# triboard-tc3x7-extension.net
KiCad netlist of a schematic drawn in Altium Designer
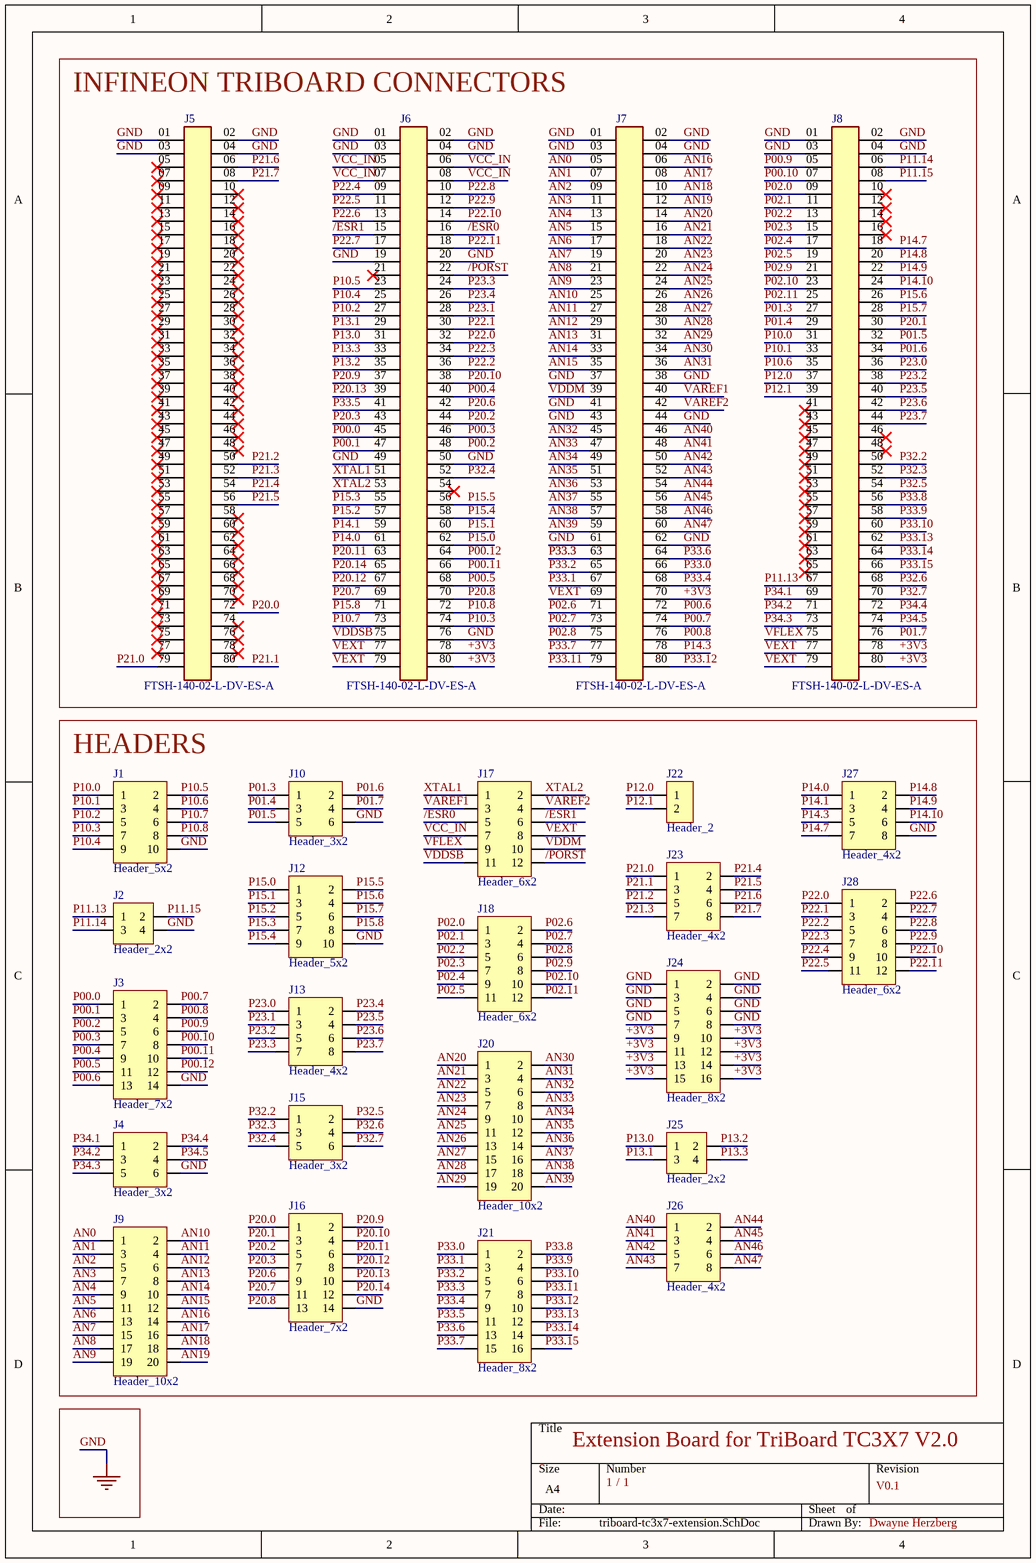
[diagram p0: triboard-tc3x7-extension.SchDoc]

(export (version "E")
  (design (tool "Eeschema 10.0.6"))
  (components
    (comp (ref "J1")
      (value "Header_5x2")
      (footprint "header_5x2")
      (libsource (lib "Shield") (part "Header_5x2"))
    )
    (comp (ref "J2")
      (value "Header_2x2")
      (footprint "Header_2x2")
      (libsource (lib "Shield") (part "Header_2x2"))
    )
    (comp (ref "J3")
      (value "Header_7x2")
      (footprint "header_7x2")
      (libsource (lib "Shield") (part "Header_7x2"))
    )
    (comp (ref "J4")
      (value "Header_3x2")
      (footprint "Header_3x2")
      (libsource (lib "Shield") (part "Header_3x2"))
    )
    (comp (ref "J5")
      (value "FTSH-140-02-L-DV-ES-A")
      (footprint "SAMTEC_FTSH-140-XX-XXX-DV-ES-A")
      (description "Board Connector")
      (fields (field (name "MANUFACTURER") "Samtec"))
      (libsource (lib "Shield") (part "FTSH-140-02-L-DV-ES-A"))
    )
    (comp (ref "J6")
      (value "FTSH-140-02-L-DV-ES-A")
      (footprint "SAMTEC_FTSH-140-XX-XXX-DV-ES-A")
      (description "Board Connector")
      (fields (field (name "MANUFACTURER") "Samtec"))
      (libsource (lib "Shield") (part "FTSH-140-02-L-DV-ES-A"))
    )
    (comp (ref "J7")
      (value "FTSH-140-02-L-DV-ES-A")
      (footprint "SAMTEC_FTSH-140-XX-XXX-DV-ES-A")
      (description "Board Connector")
      (fields (field (name "MANUFACTURER") "Samtec"))
      (libsource (lib "Shield") (part "FTSH-140-02-L-DV-ES-A"))
    )
    (comp (ref "J8")
      (value "FTSH-140-02-L-DV-ES-A")
      (footprint "SAMTEC_FTSH-140-XX-XXX-DV-ES-A")
      (description "Board Connector")
      (fields (field (name "MANUFACTURER") "Samtec"))
      (libsource (lib "Shield") (part "FTSH-140-02-L-DV-ES-A"))
    )
    (comp (ref "J9")
      (value "Header_10x2")
      (footprint "Header_10x2")
      (libsource (lib "Shield") (part "Header_10x2"))
    )
    (comp (ref "J10")
      (value "Header_3x2")
      (footprint "Header_3x2")
      (libsource (lib "Shield") (part "Header_3x2"))
    )
    (comp (ref "J12")
      (value "Header_5x2")
      (footprint "header_5x2")
      (libsource (lib "Shield") (part "Header_5x2"))
    )
    (comp (ref "J13")
      (value "Header_4x2")
      (footprint "header_4x2")
      (libsource (lib "Shield") (part "Header_4x2"))
    )
    (comp (ref "J15")
      (value "Header_3x2")
      (footprint "Header_3x2")
      (libsource (lib "Shield") (part "Header_3x2"))
    )
    (comp (ref "J16")
      (value "Header_7x2")
      (footprint "header_7x2")
      (libsource (lib "Shield") (part "Header_7x2"))
    )
    (comp (ref "J17")
      (value "Header_6x2")
      (footprint "header_6x2")
      (libsource (lib "Shield") (part "Header_6x2"))
    )
    (comp (ref "J18")
      (value "Header_6x2")
      (footprint "header_6x2")
      (libsource (lib "Shield") (part "Header_6x2"))
    )
    (comp (ref "J20")
      (value "Header_10x2")
      (footprint "Header_10x2")
      (libsource (lib "Shield") (part "Header_10x2"))
    )
    (comp (ref "J21")
      (value "Header_8x2")
      (footprint "header_8x2")
      (libsource (lib "Shield") (part "Header_8x2"))
    )
    (comp (ref "J22") (value "Header_2") (footprint "HEADER_2") (libsource (lib "Shield") (part "Header_2")))
    (comp (ref "J23")
      (value "Header_4x2")
      (footprint "header_4x2")
      (libsource (lib "Shield") (part "Header_4x2"))
    )
    (comp (ref "J24")
      (value "Header_8x2")
      (footprint "header_8x2")
      (libsource (lib "Shield") (part "Header_8x2"))
    )
    (comp (ref "J25")
      (value "Header_2x2")
      (footprint "Header_2x2")
      (libsource (lib "Shield") (part "Header_2x2"))
    )
    (comp (ref "J26")
      (value "Header_4x2")
      (footprint "header_4x2")
      (libsource (lib "Shield") (part "Header_4x2"))
    )
    (comp (ref "J27")
      (value "Header_4x2")
      (footprint "header_4x2")
      (libsource (lib "Shield") (part "Header_4x2"))
    )
    (comp (ref "J28")
      (value "Header_6x2")
      (footprint "header_6x2")
      (libsource (lib "Shield") (part "Header_6x2"))
    )
  )
  (nets
    (net (code "1") (name "/+3V3") (class "Default")
      (node (ref "J24") (pin "10") (pinfunction "10_10") (pintype "passive"))
      (node (ref "J24") (pin "11") (pinfunction "11_11") (pintype "passive"))
      (node (ref "J24") (pin "12") (pinfunction "12_12") (pintype "passive"))
      (node (ref "J24") (pin "13") (pinfunction "13_13") (pintype "passive"))
      (node (ref "J24") (pin "14") (pinfunction "14_14") (pintype "passive"))
      (node (ref "J24") (pin "15") (pinfunction "15_15") (pintype "passive"))
      (node (ref "J24") (pin "16") (pinfunction "16_16") (pintype "passive"))
      (node (ref "J24") (pin "9") (pinfunction "9_9") (pintype "passive"))
      (node (ref "J6") (pin "78") (pinfunction "78_78") (pintype "passive"))
      (node (ref "J6") (pin "80") (pinfunction "80_80") (pintype "passive"))
      (node (ref "J7") (pin "70") (pinfunction "70_70") (pintype "passive"))
      (node (ref "J8") (pin "78") (pinfunction "78_78") (pintype "passive"))
      (node (ref "J8") (pin "80") (pinfunction "80_80") (pintype "passive"))
    )
    (net (code "2") (name "/AN0") (class "Default")
      (node (ref "J7") (pin "05") (pinfunction "05_05") (pintype "passive"))
      (node (ref "J9") (pin "1") (pinfunction "1_1") (pintype "passive"))
    )
    (net (code "3") (name "/AN1") (class "Default")
      (node (ref "J7") (pin "07") (pinfunction "07_07") (pintype "passive"))
      (node (ref "J9") (pin "3") (pinfunction "3_3") (pintype "passive"))
    )
    (net (code "4") (name "/AN2") (class "Default")
      (node (ref "J7") (pin "09") (pinfunction "09_09") (pintype "passive"))
      (node (ref "J9") (pin "5") (pinfunction "5_5") (pintype "passive"))
    )
    (net (code "5") (name "/AN3") (class "Default")
      (node (ref "J7") (pin "11") (pinfunction "11_11") (pintype "passive"))
      (node (ref "J9") (pin "7") (pinfunction "7_7") (pintype "passive"))
    )
    (net (code "6") (name "/AN4") (class "Default")
      (node (ref "J7") (pin "13") (pinfunction "13_13") (pintype "passive"))
      (node (ref "J9") (pin "9") (pinfunction "9_9") (pintype "passive"))
    )
    (net (code "7") (name "/AN5") (class "Default")
      (node (ref "J7") (pin "15") (pinfunction "15_15") (pintype "passive"))
      (node (ref "J9") (pin "11") (pinfunction "11_11") (pintype "passive"))
    )
    (net (code "8") (name "/AN6") (class "Default")
      (node (ref "J7") (pin "17") (pinfunction "17_17") (pintype "passive"))
      (node (ref "J9") (pin "13") (pinfunction "13_13") (pintype "passive"))
    )
    (net (code "9") (name "/AN7") (class "Default")
      (node (ref "J7") (pin "19") (pinfunction "19_19") (pintype "passive"))
      (node (ref "J9") (pin "15") (pinfunction "15_15") (pintype "passive"))
    )
    (net (code "10") (name "/AN8") (class "Default")
      (node (ref "J7") (pin "21") (pinfunction "21_21") (pintype "passive"))
      (node (ref "J9") (pin "17") (pinfunction "17_17") (pintype "passive"))
    )
    (net (code "11") (name "/AN9") (class "Default")
      (node (ref "J7") (pin "23") (pinfunction "23_23") (pintype "passive"))
      (node (ref "J9") (pin "19") (pinfunction "19_19") (pintype "passive"))
    )
    (net (code "12") (name "/AN10") (class "Default")
      (node (ref "J7") (pin "25") (pinfunction "25_25") (pintype "passive"))
      (node (ref "J9") (pin "2") (pinfunction "2_2") (pintype "passive"))
    )
    (net (code "13") (name "/AN11") (class "Default")
      (node (ref "J7") (pin "27") (pinfunction "27_27") (pintype "passive"))
      (node (ref "J9") (pin "4") (pinfunction "4_4") (pintype "passive"))
    )
    (net (code "14") (name "/AN12") (class "Default")
      (node (ref "J7") (pin "29") (pinfunction "29_29") (pintype "passive"))
      (node (ref "J9") (pin "6") (pinfunction "6_6") (pintype "passive"))
    )
    (net (code "15") (name "/AN13") (class "Default")
      (node (ref "J7") (pin "31") (pinfunction "31_31") (pintype "passive"))
      (node (ref "J9") (pin "8") (pinfunction "8_8") (pintype "passive"))
    )
    (net (code "16") (name "/AN14") (class "Default")
      (node (ref "J7") (pin "33") (pinfunction "33_33") (pintype "passive"))
      (node (ref "J9") (pin "10") (pinfunction "10_10") (pintype "passive"))
    )
    (net (code "17") (name "/AN15") (class "Default")
      (node (ref "J7") (pin "35") (pinfunction "35_35") (pintype "passive"))
      (node (ref "J9") (pin "12") (pinfunction "12_12") (pintype "passive"))
    )
    (net (code "18") (name "/AN16") (class "Default")
      (node (ref "J7") (pin "06") (pinfunction "06_06") (pintype "passive"))
      (node (ref "J9") (pin "14") (pinfunction "14_14") (pintype "passive"))
    )
    (net (code "19") (name "/AN17") (class "Default")
      (node (ref "J7") (pin "08") (pinfunction "08_08") (pintype "passive"))
      (node (ref "J9") (pin "16") (pinfunction "16_16") (pintype "passive"))
    )
    (net (code "20") (name "/AN18") (class "Default")
      (node (ref "J7") (pin "10") (pinfunction "10_10") (pintype "passive"))
      (node (ref "J9") (pin "18") (pinfunction "18_18") (pintype "passive"))
    )
    (net (code "21") (name "/AN19") (class "Default")
      (node (ref "J7") (pin "12") (pinfunction "12_12") (pintype "passive"))
      (node (ref "J9") (pin "20") (pinfunction "20_20") (pintype "passive"))
    )
    (net (code "22") (name "/AN20") (class "Default")
      (node (ref "J20") (pin "1") (pinfunction "1_1") (pintype "passive"))
      (node (ref "J7") (pin "14") (pinfunction "14_14") (pintype "passive"))
    )
    (net (code "23") (name "/AN21") (class "Default")
      (node (ref "J20") (pin "3") (pinfunction "3_3") (pintype "passive"))
      (node (ref "J7") (pin "16") (pinfunction "16_16") (pintype "passive"))
    )
    (net (code "24") (name "/AN22") (class "Default")
      (node (ref "J20") (pin "5") (pinfunction "5_5") (pintype "passive"))
      (node (ref "J7") (pin "18") (pinfunction "18_18") (pintype "passive"))
    )
    (net (code "25") (name "/AN23") (class "Default")
      (node (ref "J20") (pin "7") (pinfunction "7_7") (pintype "passive"))
      (node (ref "J7") (pin "20") (pinfunction "20_20") (pintype "passive"))
    )
    (net (code "26") (name "/AN24") (class "Default")
      (node (ref "J20") (pin "9") (pinfunction "9_9") (pintype "passive"))
      (node (ref "J7") (pin "22") (pinfunction "22_22") (pintype "passive"))
    )
    (net (code "27") (name "/AN25") (class "Default")
      (node (ref "J20") (pin "11") (pinfunction "11_11") (pintype "passive"))
      (node (ref "J7") (pin "24") (pinfunction "24_24") (pintype "passive"))
    )
    (net (code "28") (name "/AN26") (class "Default")
      (node (ref "J20") (pin "13") (pinfunction "13_13") (pintype "passive"))
      (node (ref "J7") (pin "26") (pinfunction "26_26") (pintype "passive"))
    )
    (net (code "29") (name "/AN27") (class "Default")
      (node (ref "J20") (pin "15") (pinfunction "15_15") (pintype "passive"))
      (node (ref "J7") (pin "28") (pinfunction "28_28") (pintype "passive"))
    )
    (net (code "30") (name "/AN28") (class "Default")
      (node (ref "J20") (pin "17") (pinfunction "17_17") (pintype "passive"))
      (node (ref "J7") (pin "30") (pinfunction "30_30") (pintype "passive"))
    )
    (net (code "31") (name "/AN29") (class "Default")
      (node (ref "J20") (pin "19") (pinfunction "19_19") (pintype "passive"))
      (node (ref "J7") (pin "32") (pinfunction "32_32") (pintype "passive"))
    )
    (net (code "32") (name "/AN30") (class "Default")
      (node (ref "J20") (pin "2") (pinfunction "2_2") (pintype "passive"))
      (node (ref "J7") (pin "34") (pinfunction "34_34") (pintype "passive"))
    )
    (net (code "33") (name "/AN31") (class "Default")
      (node (ref "J20") (pin "4") (pinfunction "4_4") (pintype "passive"))
      (node (ref "J7") (pin "36") (pinfunction "36_36") (pintype "passive"))
    )
    (net (code "34") (name "/AN32") (class "Default")
      (node (ref "J20") (pin "6") (pinfunction "6_6") (pintype "passive"))
      (node (ref "J7") (pin "45") (pinfunction "45_45") (pintype "passive"))
    )
    (net (code "35") (name "/AN33") (class "Default")
      (node (ref "J20") (pin "8") (pinfunction "8_8") (pintype "passive"))
      (node (ref "J7") (pin "47") (pinfunction "47_47") (pintype "passive"))
    )
    (net (code "36") (name "/AN34") (class "Default")
      (node (ref "J20") (pin "10") (pinfunction "10_10") (pintype "passive"))
      (node (ref "J7") (pin "49") (pinfunction "49_49") (pintype "passive"))
    )
    (net (code "37") (name "/AN35") (class "Default")
      (node (ref "J20") (pin "12") (pinfunction "12_12") (pintype "passive"))
      (node (ref "J7") (pin "51") (pinfunction "51_51") (pintype "passive"))
    )
    (net (code "38") (name "/AN36") (class "Default")
      (node (ref "J20") (pin "14") (pinfunction "14_14") (pintype "passive"))
      (node (ref "J7") (pin "53") (pinfunction "53_53") (pintype "passive"))
    )
    (net (code "39") (name "/AN37") (class "Default")
      (node (ref "J20") (pin "16") (pinfunction "16_16") (pintype "passive"))
      (node (ref "J7") (pin "55") (pinfunction "55_55") (pintype "passive"))
    )
    (net (code "40") (name "/AN38") (class "Default")
      (node (ref "J20") (pin "18") (pinfunction "18_18") (pintype "passive"))
      (node (ref "J7") (pin "57") (pinfunction "57_57") (pintype "passive"))
    )
    (net (code "41") (name "/AN39") (class "Default")
      (node (ref "J20") (pin "20") (pinfunction "20_20") (pintype "passive"))
      (node (ref "J7") (pin "59") (pinfunction "59_59") (pintype "passive"))
    )
    (net (code "42") (name "/AN40") (class "Default")
      (node (ref "J26") (pin "1") (pinfunction "1_1") (pintype "passive"))
      (node (ref "J7") (pin "46") (pinfunction "46_46") (pintype "passive"))
    )
    (net (code "43") (name "/AN41") (class "Default")
      (node (ref "J26") (pin "3") (pinfunction "3_3") (pintype "passive"))
      (node (ref "J7") (pin "48") (pinfunction "48_48") (pintype "passive"))
    )
    (net (code "44") (name "/AN42") (class "Default")
      (node (ref "J26") (pin "5") (pinfunction "5_5") (pintype "passive"))
      (node (ref "J7") (pin "50") (pinfunction "50_50") (pintype "passive"))
    )
    (net (code "45") (name "/AN43") (class "Default")
      (node (ref "J26") (pin "7") (pinfunction "7_7") (pintype "passive"))
      (node (ref "J7") (pin "52") (pinfunction "52_52") (pintype "passive"))
    )
    (net (code "46") (name "/AN44") (class "Default")
      (node (ref "J26") (pin "2") (pinfunction "2_2") (pintype "passive"))
      (node (ref "J7") (pin "54") (pinfunction "54_54") (pintype "passive"))
    )
    (net (code "47") (name "/AN45") (class "Default")
      (node (ref "J26") (pin "4") (pinfunction "4_4") (pintype "passive"))
      (node (ref "J7") (pin "56") (pinfunction "56_56") (pintype "passive"))
    )
    (net (code "48") (name "/AN46") (class "Default")
      (node (ref "J26") (pin "6") (pinfunction "6_6") (pintype "passive"))
      (node (ref "J7") (pin "58") (pinfunction "58_58") (pintype "passive"))
    )
    (net (code "49") (name "/AN47") (class "Default")
      (node (ref "J26") (pin "8") (pinfunction "8_8") (pintype "passive"))
      (node (ref "J7") (pin "60") (pinfunction "60_60") (pintype "passive"))
    )
    (net (code "50") (name "/P00.0") (class "Default")
      (node (ref "J3") (pin "1") (pinfunction "1_1") (pintype "passive"))
      (node (ref "J6") (pin "45") (pinfunction "45_45") (pintype "passive"))
    )
    (net (code "51") (name "/P00.1") (class "Default")
      (node (ref "J3") (pin "3") (pinfunction "3_3") (pintype "passive"))
      (node (ref "J6") (pin "47") (pinfunction "47_47") (pintype "passive"))
    )
    (net (code "52") (name "/P00.2") (class "Default")
      (node (ref "J3") (pin "5") (pinfunction "5_5") (pintype "passive"))
      (node (ref "J6") (pin "48") (pinfunction "48_48") (pintype "passive"))
    )
    (net (code "53") (name "/P00.3") (class "Default")
      (node (ref "J3") (pin "7") (pinfunction "7_7") (pintype "passive"))
      (node (ref "J6") (pin "46") (pinfunction "46_46") (pintype "passive"))
    )
    (net (code "54") (name "/P00.4") (class "Default")
      (node (ref "J3") (pin "9") (pinfunction "9_9") (pintype "passive"))
      (node (ref "J6") (pin "40") (pinfunction "40_40") (pintype "passive"))
    )
    (net (code "55") (name "/P00.5") (class "Default")
      (node (ref "J3") (pin "11") (pinfunction "11_11") (pintype "passive"))
      (node (ref "J6") (pin "68") (pinfunction "68_68") (pintype "passive"))
    )
    (net (code "56") (name "/P00.6") (class "Default")
      (node (ref "J3") (pin "13") (pinfunction "13_13") (pintype "passive"))
      (node (ref "J7") (pin "72") (pinfunction "72_72") (pintype "passive"))
    )
    (net (code "57") (name "/P00.7") (class "Default")
      (node (ref "J3") (pin "2") (pinfunction "2_2") (pintype "passive"))
      (node (ref "J7") (pin "74") (pinfunction "74_74") (pintype "passive"))
    )
    (net (code "58") (name "/P00.8") (class "Default")
      (node (ref "J3") (pin "4") (pinfunction "4_4") (pintype "passive"))
      (node (ref "J7") (pin "76") (pinfunction "76_76") (pintype "passive"))
    )
    (net (code "59") (name "/P00.9") (class "Default")
      (node (ref "J3") (pin "6") (pinfunction "6_6") (pintype "passive"))
      (node (ref "J8") (pin "05") (pinfunction "05_05") (pintype "passive"))
    )
    (net (code "60") (name "/P00.10") (class "Default")
      (node (ref "J3") (pin "8") (pinfunction "8_8") (pintype "passive"))
      (node (ref "J8") (pin "07") (pinfunction "07_07") (pintype "passive"))
    )
    (net (code "61") (name "/P00.11") (class "Default")
      (node (ref "J3") (pin "10") (pinfunction "10_10") (pintype "passive"))
      (node (ref "J6") (pin "66") (pinfunction "66_66") (pintype "passive"))
    )
    (net (code "62") (name "/P00.12") (class "Default")
      (node (ref "J3") (pin "12") (pinfunction "12_12") (pintype "passive"))
      (node (ref "J6") (pin "64") (pinfunction "64_64") (pintype "passive"))
    )
    (net (code "63") (name "/P01.3") (class "Default")
      (node (ref "J10") (pin "1") (pinfunction "1_1") (pintype "passive"))
      (node (ref "J8") (pin "27") (pinfunction "27_27") (pintype "passive"))
    )
    (net (code "64") (name "/P01.4") (class "Default")
      (node (ref "J10") (pin "3") (pinfunction "3_3") (pintype "passive"))
      (node (ref "J8") (pin "29") (pinfunction "29_29") (pintype "passive"))
    )
    (net (code "65") (name "/P01.5") (class "Default")
      (node (ref "J10") (pin "5") (pinfunction "5_5") (pintype "passive"))
      (node (ref "J8") (pin "32") (pinfunction "32_32") (pintype "passive"))
    )
    (net (code "66") (name "/P01.6") (class "Default")
      (node (ref "J10") (pin "2") (pinfunction "2_2") (pintype "passive"))
      (node (ref "J8") (pin "34") (pinfunction "34_34") (pintype "passive"))
    )
    (net (code "67") (name "/P01.7") (class "Default")
      (node (ref "J10") (pin "4") (pinfunction "4_4") (pintype "passive"))
      (node (ref "J8") (pin "76") (pinfunction "76_76") (pintype "passive"))
    )
    (net (code "68") (name "/P02.0") (class "Default")
      (node (ref "J18") (pin "1") (pinfunction "1_1") (pintype "passive"))
      (node (ref "J8") (pin "09") (pinfunction "09_09") (pintype "passive"))
    )
    (net (code "69") (name "/P02.1") (class "Default")
      (node (ref "J18") (pin "3") (pinfunction "3_3") (pintype "passive"))
      (node (ref "J8") (pin "11") (pinfunction "11_11") (pintype "passive"))
    )
    (net (code "70") (name "/P02.2") (class "Default")
      (node (ref "J18") (pin "5") (pinfunction "5_5") (pintype "passive"))
      (node (ref "J8") (pin "13") (pinfunction "13_13") (pintype "passive"))
    )
    (net (code "71") (name "/P02.3") (class "Default")
      (node (ref "J18") (pin "7") (pinfunction "7_7") (pintype "passive"))
      (node (ref "J8") (pin "15") (pinfunction "15_15") (pintype "passive"))
    )
    (net (code "72") (name "/P02.4") (class "Default")
      (node (ref "J18") (pin "9") (pinfunction "9_9") (pintype "passive"))
      (node (ref "J8") (pin "17") (pinfunction "17_17") (pintype "passive"))
    )
    (net (code "73") (name "/P02.5") (class "Default")
      (node (ref "J18") (pin "11") (pinfunction "11_11") (pintype "passive"))
      (node (ref "J8") (pin "19") (pinfunction "19_19") (pintype "passive"))
    )
    (net (code "74") (name "/P02.6") (class "Default")
      (node (ref "J18") (pin "2") (pinfunction "2_2") (pintype "passive"))
      (node (ref "J7") (pin "71") (pinfunction "71_71") (pintype "passive"))
    )
    (net (code "75") (name "/P02.7") (class "Default")
      (node (ref "J18") (pin "4") (pinfunction "4_4") (pintype "passive"))
      (node (ref "J7") (pin "73") (pinfunction "73_73") (pintype "passive"))
    )
    (net (code "76") (name "/P02.8") (class "Default")
      (node (ref "J18") (pin "6") (pinfunction "6_6") (pintype "passive"))
      (node (ref "J7") (pin "75") (pinfunction "75_75") (pintype "passive"))
    )
    (net (code "77") (name "/P02.9") (class "Default")
      (node (ref "J18") (pin "8") (pinfunction "8_8") (pintype "passive"))
      (node (ref "J8") (pin "21") (pinfunction "21_21") (pintype "passive"))
    )
    (net (code "78") (name "/P02.10") (class "Default")
      (node (ref "J18") (pin "10") (pinfunction "10_10") (pintype "passive"))
      (node (ref "J8") (pin "23") (pinfunction "23_23") (pintype "passive"))
    )
    (net (code "79") (name "/P02.11") (class "Default")
      (node (ref "J18") (pin "12") (pinfunction "12_12") (pintype "passive"))
      (node (ref "J8") (pin "25") (pinfunction "25_25") (pintype "passive"))
    )
    (net (code "80") (name "/P10.0") (class "Default")
      (node (ref "J1") (pin "1") (pinfunction "1_1") (pintype "passive"))
      (node (ref "J8") (pin "31") (pinfunction "31_31") (pintype "passive"))
    )
    (net (code "81") (name "/P10.1") (class "Default")
      (node (ref "J1") (pin "3") (pinfunction "3_3") (pintype "passive"))
      (node (ref "J8") (pin "33") (pinfunction "33_33") (pintype "passive"))
    )
    (net (code "82") (name "/P10.2") (class "Default")
      (node (ref "J1") (pin "5") (pinfunction "5_5") (pintype "passive"))
      (node (ref "J6") (pin "27") (pinfunction "27_27") (pintype "passive"))
    )
    (net (code "83") (name "/P10.3") (class "Default")
      (node (ref "J1") (pin "7") (pinfunction "7_7") (pintype "passive"))
      (node (ref "J6") (pin "74") (pinfunction "74_74") (pintype "passive"))
    )
    (net (code "84") (name "/P10.4") (class "Default")
      (node (ref "J1") (pin "9") (pinfunction "9_9") (pintype "passive"))
      (node (ref "J6") (pin "25") (pinfunction "25_25") (pintype "passive"))
    )
    (net (code "85") (name "/P10.5") (class "Default")
      (node (ref "J1") (pin "2") (pinfunction "2_2") (pintype "passive"))
      (node (ref "J6") (pin "23") (pinfunction "23_23") (pintype "passive"))
    )
    (net (code "86") (name "/P10.6") (class "Default")
      (node (ref "J1") (pin "4") (pinfunction "4_4") (pintype "passive"))
      (node (ref "J8") (pin "35") (pinfunction "35_35") (pintype "passive"))
    )
    (net (code "87") (name "/P10.7") (class "Default")
      (node (ref "J1") (pin "6") (pinfunction "6_6") (pintype "passive"))
      (node (ref "J6") (pin "73") (pinfunction "73_73") (pintype "passive"))
    )
    (net (code "88") (name "/P10.8") (class "Default")
      (node (ref "J1") (pin "8") (pinfunction "8_8") (pintype "passive"))
      (node (ref "J6") (pin "72") (pinfunction "72_72") (pintype "passive"))
    )
    (net (code "89") (name "/P11.13") (class "Default")
      (node (ref "J2") (pin "1") (pinfunction "1_1") (pintype "passive"))
      (node (ref "J8") (pin "67") (pinfunction "67_67") (pintype "passive"))
    )
    (net (code "90") (name "/P11.14") (class "Default")
      (node (ref "J2") (pin "3") (pinfunction "3_3") (pintype "passive"))
      (node (ref "J8") (pin "06") (pinfunction "06_06") (pintype "passive"))
    )
    (net (code "91") (name "/P11.15") (class "Default")
      (node (ref "J2") (pin "2") (pinfunction "2_2") (pintype "passive"))
      (node (ref "J8") (pin "08") (pinfunction "08_08") (pintype "passive"))
    )
    (net (code "92") (name "/P12.0") (class "Default")
      (node (ref "J22") (pin "1") (pinfunction "1_1") (pintype "passive"))
      (node (ref "J8") (pin "37") (pinfunction "37_37") (pintype "passive"))
    )
    (net (code "93") (name "/P12.1") (class "Default")
      (node (ref "J22") (pin "2") (pinfunction "2_2") (pintype "passive"))
      (node (ref "J8") (pin "39") (pinfunction "39_39") (pintype "passive"))
    )
    (net (code "94") (name "/P13.0") (class "Default")
      (node (ref "J25") (pin "1") (pinfunction "1_1") (pintype "passive"))
      (node (ref "J6") (pin "31") (pinfunction "31_31") (pintype "passive"))
    )
    (net (code "95") (name "/P13.1") (class "Default")
      (node (ref "J25") (pin "3") (pinfunction "3_3") (pintype "passive"))
      (node (ref "J6") (pin "29") (pinfunction "29_29") (pintype "passive"))
    )
    (net (code "96") (name "/P13.2") (class "Default")
      (node (ref "J25") (pin "2") (pinfunction "2_2") (pintype "passive"))
      (node (ref "J6") (pin "35") (pinfunction "35_35") (pintype "passive"))
    )
    (net (code "97") (name "/P13.3") (class "Default")
      (node (ref "J25") (pin "4") (pinfunction "4_4") (pintype "passive"))
      (node (ref "J6") (pin "33") (pinfunction "33_33") (pintype "passive"))
    )
    (net (code "98") (name "/P14.0") (class "Default")
      (node (ref "J27") (pin "1") (pinfunction "1_1") (pintype "passive"))
      (node (ref "J6") (pin "61") (pinfunction "61_61") (pintype "passive"))
    )
    (net (code "99") (name "/P14.1") (class "Default")
      (node (ref "J27") (pin "3") (pinfunction "3_3") (pintype "passive"))
      (node (ref "J6") (pin "59") (pinfunction "59_59") (pintype "passive"))
    )
    (net (code "100") (name "/P14.3") (class "Default")
      (node (ref "J27") (pin "5") (pinfunction "5_5") (pintype "passive"))
      (node (ref "J7") (pin "78") (pinfunction "78_78") (pintype "passive"))
    )
    (net (code "101") (name "/P14.7") (class "Default")
      (node (ref "J27") (pin "7") (pinfunction "7_7") (pintype "passive"))
      (node (ref "J8") (pin "18") (pinfunction "18_18") (pintype "passive"))
    )
    (net (code "102") (name "/P14.8") (class "Default")
      (node (ref "J27") (pin "2") (pinfunction "2_2") (pintype "passive"))
      (node (ref "J8") (pin "20") (pinfunction "20_20") (pintype "passive"))
    )
    (net (code "103") (name "/P14.9") (class "Default")
      (node (ref "J27") (pin "4") (pinfunction "4_4") (pintype "passive"))
      (node (ref "J8") (pin "22") (pinfunction "22_22") (pintype "passive"))
    )
    (net (code "104") (name "/P14.10") (class "Default")
      (node (ref "J27") (pin "6") (pinfunction "6_6") (pintype "passive"))
      (node (ref "J8") (pin "24") (pinfunction "24_24") (pintype "passive"))
    )
    (net (code "105") (name "/P15.0") (class "Default")
      (node (ref "J12") (pin "1") (pinfunction "1_1") (pintype "passive"))
      (node (ref "J6") (pin "62") (pinfunction "62_62") (pintype "passive"))
    )
    (net (code "106") (name "/P15.1") (class "Default")
      (node (ref "J12") (pin "3") (pinfunction "3_3") (pintype "passive"))
      (node (ref "J6") (pin "60") (pinfunction "60_60") (pintype "passive"))
    )
    (net (code "107") (name "/P15.2") (class "Default")
      (node (ref "J12") (pin "5") (pinfunction "5_5") (pintype "passive"))
      (node (ref "J6") (pin "57") (pinfunction "57_57") (pintype "passive"))
    )
    (net (code "108") (name "/P15.3") (class "Default")
      (node (ref "J12") (pin "7") (pinfunction "7_7") (pintype "passive"))
      (node (ref "J6") (pin "55") (pinfunction "55_55") (pintype "passive"))
    )
    (net (code "109") (name "/P15.4") (class "Default")
      (node (ref "J12") (pin "9") (pinfunction "9_9") (pintype "passive"))
      (node (ref "J6") (pin "58") (pinfunction "58_58") (pintype "passive"))
    )
    (net (code "110") (name "/P15.5") (class "Default")
      (node (ref "J12") (pin "2") (pinfunction "2_2") (pintype "passive"))
      (node (ref "J6") (pin "56") (pinfunction "56_56") (pintype "passive"))
    )
    (net (code "111") (name "/P15.6") (class "Default")
      (node (ref "J12") (pin "4") (pinfunction "4_4") (pintype "passive"))
      (node (ref "J8") (pin "26") (pinfunction "26_26") (pintype "passive"))
    )
    (net (code "112") (name "/P15.7") (class "Default")
      (node (ref "J12") (pin "6") (pinfunction "6_6") (pintype "passive"))
      (node (ref "J8") (pin "28") (pinfunction "28_28") (pintype "passive"))
    )
    (net (code "113") (name "/P15.8") (class "Default")
      (node (ref "J12") (pin "8") (pinfunction "8_8") (pintype "passive"))
      (node (ref "J6") (pin "71") (pinfunction "71_71") (pintype "passive"))
    )
    (net (code "114") (name "/P20.0") (class "Default")
      (node (ref "J16") (pin "1") (pinfunction "1_1") (pintype "passive"))
      (node (ref "J5") (pin "72") (pinfunction "72_72") (pintype "passive"))
    )
    (net (code "115") (name "/P20.1") (class "Default")
      (node (ref "J16") (pin "3") (pinfunction "3_3") (pintype "passive"))
      (node (ref "J8") (pin "30") (pinfunction "30_30") (pintype "passive"))
    )
    (net (code "116") (name "/P20.2") (class "Default")
      (node (ref "J16") (pin "5") (pinfunction "5_5") (pintype "passive"))
      (node (ref "J6") (pin "44") (pinfunction "44_44") (pintype "passive"))
    )
    (net (code "117") (name "/P20.3") (class "Default")
      (node (ref "J16") (pin "7") (pinfunction "7_7") (pintype "passive"))
      (node (ref "J6") (pin "43") (pinfunction "43_43") (pintype "passive"))
    )
    (net (code "118") (name "/P20.6") (class "Default")
      (node (ref "J16") (pin "9") (pinfunction "9_9") (pintype "passive"))
      (node (ref "J6") (pin "42") (pinfunction "42_42") (pintype "passive"))
    )
    (net (code "119") (name "/P20.7") (class "Default")
      (node (ref "J16") (pin "11") (pinfunction "11_11") (pintype "passive"))
      (node (ref "J6") (pin "69") (pinfunction "69_69") (pintype "passive"))
    )
    (net (code "120") (name "/P20.8") (class "Default")
      (node (ref "J16") (pin "13") (pinfunction "13_13") (pintype "passive"))
      (node (ref "J6") (pin "70") (pinfunction "70_70") (pintype "passive"))
    )
    (net (code "121") (name "/P20.9") (class "Default")
      (node (ref "J16") (pin "2") (pinfunction "2_2") (pintype "passive"))
      (node (ref "J6") (pin "37") (pinfunction "37_37") (pintype "passive"))
    )
    (net (code "122") (name "/P20.10") (class "Default")
      (node (ref "J16") (pin "4") (pinfunction "4_4") (pintype "passive"))
      (node (ref "J6") (pin "38") (pinfunction "38_38") (pintype "passive"))
    )
    (net (code "123") (name "/P20.11") (class "Default")
      (node (ref "J16") (pin "6") (pinfunction "6_6") (pintype "passive"))
      (node (ref "J6") (pin "63") (pinfunction "63_63") (pintype "passive"))
    )
    (net (code "124") (name "/P20.12") (class "Default")
      (node (ref "J16") (pin "8") (pinfunction "8_8") (pintype "passive"))
      (node (ref "J6") (pin "67") (pinfunction "67_67") (pintype "passive"))
    )
    (net (code "125") (name "/P20.13") (class "Default")
      (node (ref "J16") (pin "10") (pinfunction "10_10") (pintype "passive"))
      (node (ref "J6") (pin "39") (pinfunction "39_39") (pintype "passive"))
    )
    (net (code "126") (name "/P20.14") (class "Default")
      (node (ref "J16") (pin "12") (pinfunction "12_12") (pintype "passive"))
      (node (ref "J6") (pin "65") (pinfunction "65_65") (pintype "passive"))
    )
    (net (code "127") (name "/P21.0") (class "Default")
      (node (ref "J23") (pin "1") (pinfunction "1_1") (pintype "passive"))
      (node (ref "J5") (pin "79") (pinfunction "79_79") (pintype "passive"))
    )
    (net (code "128") (name "/P21.1") (class "Default")
      (node (ref "J23") (pin "3") (pinfunction "3_3") (pintype "passive"))
      (node (ref "J5") (pin "80") (pinfunction "80_80") (pintype "passive"))
    )
    (net (code "129") (name "/P21.2") (class "Default")
      (node (ref "J23") (pin "5") (pinfunction "5_5") (pintype "passive"))
      (node (ref "J5") (pin "50") (pinfunction "50_50") (pintype "passive"))
    )
    (net (code "130") (name "/P21.3") (class "Default")
      (node (ref "J23") (pin "7") (pinfunction "7_7") (pintype "passive"))
      (node (ref "J5") (pin "52") (pinfunction "52_52") (pintype "passive"))
    )
    (net (code "131") (name "/P21.4") (class "Default")
      (node (ref "J23") (pin "2") (pinfunction "2_2") (pintype "passive"))
      (node (ref "J5") (pin "54") (pinfunction "54_54") (pintype "passive"))
    )
    (net (code "132") (name "/P21.5") (class "Default")
      (node (ref "J23") (pin "4") (pinfunction "4_4") (pintype "passive"))
      (node (ref "J5") (pin "56") (pinfunction "56_56") (pintype "passive"))
    )
    (net (code "133") (name "/P21.6") (class "Default")
      (node (ref "J23") (pin "6") (pinfunction "6_6") (pintype "passive"))
      (node (ref "J5") (pin "06") (pinfunction "06_06") (pintype "passive"))
    )
    (net (code "134") (name "/P21.7") (class "Default")
      (node (ref "J23") (pin "8") (pinfunction "8_8") (pintype "passive"))
      (node (ref "J5") (pin "08") (pinfunction "08_08") (pintype "passive"))
    )
    (net (code "135") (name "/P22.0") (class "Default")
      (node (ref "J28") (pin "1") (pinfunction "1_1") (pintype "passive"))
      (node (ref "J6") (pin "32") (pinfunction "32_32") (pintype "passive"))
    )
    (net (code "136") (name "/P22.1") (class "Default")
      (node (ref "J28") (pin "3") (pinfunction "3_3") (pintype "passive"))
      (node (ref "J6") (pin "30") (pinfunction "30_30") (pintype "passive"))
    )
    (net (code "137") (name "/P22.2") (class "Default")
      (node (ref "J28") (pin "5") (pinfunction "5_5") (pintype "passive"))
      (node (ref "J6") (pin "36") (pinfunction "36_36") (pintype "passive"))
    )
    (net (code "138") (name "/P22.3") (class "Default")
      (node (ref "J28") (pin "7") (pinfunction "7_7") (pintype "passive"))
      (node (ref "J6") (pin "34") (pinfunction "34_34") (pintype "passive"))
    )
    (net (code "139") (name "/P22.4") (class "Default")
      (node (ref "J28") (pin "9") (pinfunction "9_9") (pintype "passive"))
      (node (ref "J6") (pin "09") (pinfunction "09_09") (pintype "passive"))
    )
    (net (code "140") (name "/P22.5") (class "Default")
      (node (ref "J28") (pin "11") (pinfunction "11_11") (pintype "passive"))
      (node (ref "J6") (pin "11") (pinfunction "11_11") (pintype "passive"))
    )
    (net (code "141") (name "/P22.6") (class "Default")
      (node (ref "J28") (pin "2") (pinfunction "2_2") (pintype "passive"))
      (node (ref "J6") (pin "13") (pinfunction "13_13") (pintype "passive"))
    )
    (net (code "142") (name "/P22.7") (class "Default")
      (node (ref "J28") (pin "4") (pinfunction "4_4") (pintype "passive"))
      (node (ref "J6") (pin "17") (pinfunction "17_17") (pintype "passive"))
    )
    (net (code "143") (name "/P22.8") (class "Default")
      (node (ref "J28") (pin "6") (pinfunction "6_6") (pintype "passive"))
      (node (ref "J6") (pin "10") (pinfunction "10_10") (pintype "passive"))
    )
    (net (code "144") (name "/P22.9") (class "Default")
      (node (ref "J28") (pin "8") (pinfunction "8_8") (pintype "passive"))
      (node (ref "J6") (pin "12") (pinfunction "12_12") (pintype "passive"))
    )
    (net (code "145") (name "/P22.10") (class "Default")
      (node (ref "J28") (pin "10") (pinfunction "10_10") (pintype "passive"))
      (node (ref "J6") (pin "14") (pinfunction "14_14") (pintype "passive"))
    )
    (net (code "146") (name "/P22.11") (class "Default")
      (node (ref "J28") (pin "12") (pinfunction "12_12") (pintype "passive"))
      (node (ref "J6") (pin "18") (pinfunction "18_18") (pintype "passive"))
    )
    (net (code "147") (name "/P23.0") (class "Default")
      (node (ref "J13") (pin "1") (pinfunction "1_1") (pintype "passive"))
      (node (ref "J8") (pin "36") (pinfunction "36_36") (pintype "passive"))
    )
    (net (code "148") (name "/P23.1") (class "Default")
      (node (ref "J13") (pin "3") (pinfunction "3_3") (pintype "passive"))
      (node (ref "J6") (pin "28") (pinfunction "28_28") (pintype "passive"))
    )
    (net (code "149") (name "/P23.2") (class "Default")
      (node (ref "J13") (pin "5") (pinfunction "5_5") (pintype "passive"))
      (node (ref "J8") (pin "38") (pinfunction "38_38") (pintype "passive"))
    )
    (net (code "150") (name "/P23.3") (class "Default")
      (node (ref "J13") (pin "7") (pinfunction "7_7") (pintype "passive"))
      (node (ref "J6") (pin "24") (pinfunction "24_24") (pintype "passive"))
    )
    (net (code "151") (name "/P23.4") (class "Default")
      (node (ref "J13") (pin "2") (pinfunction "2_2") (pintype "passive"))
      (node (ref "J6") (pin "26") (pinfunction "26_26") (pintype "passive"))
    )
    (net (code "152") (name "/P23.5") (class "Default")
      (node (ref "J13") (pin "4") (pinfunction "4_4") (pintype "passive"))
      (node (ref "J8") (pin "40") (pinfunction "40_40") (pintype "passive"))
    )
    (net (code "153") (name "/P23.6") (class "Default")
      (node (ref "J13") (pin "6") (pinfunction "6_6") (pintype "passive"))
      (node (ref "J8") (pin "42") (pinfunction "42_42") (pintype "passive"))
    )
    (net (code "154") (name "/P23.7") (class "Default")
      (node (ref "J13") (pin "8") (pinfunction "8_8") (pintype "passive"))
      (node (ref "J8") (pin "44") (pinfunction "44_44") (pintype "passive"))
    )
    (net (code "155") (name "/P32.2") (class "Default")
      (node (ref "J15") (pin "1") (pinfunction "1_1") (pintype "passive"))
      (node (ref "J8") (pin "50") (pinfunction "50_50") (pintype "passive"))
    )
    (net (code "156") (name "/P32.3") (class "Default")
      (node (ref "J15") (pin "3") (pinfunction "3_3") (pintype "passive"))
      (node (ref "J8") (pin "52") (pinfunction "52_52") (pintype "passive"))
    )
    (net (code "157") (name "/P32.4") (class "Default")
      (node (ref "J15") (pin "5") (pinfunction "5_5") (pintype "passive"))
      (node (ref "J6") (pin "52") (pinfunction "52_52") (pintype "passive"))
    )
    (net (code "158") (name "/P32.5") (class "Default")
      (node (ref "J15") (pin "2") (pinfunction "2_2") (pintype "passive"))
      (node (ref "J8") (pin "54") (pinfunction "54_54") (pintype "passive"))
    )
    (net (code "159") (name "/P32.6") (class "Default")
      (node (ref "J15") (pin "4") (pinfunction "4_4") (pintype "passive"))
      (node (ref "J8") (pin "68") (pinfunction "68_68") (pintype "passive"))
    )
    (net (code "160") (name "/P32.7") (class "Default")
      (node (ref "J15") (pin "6") (pinfunction "6_6") (pintype "passive"))
      (node (ref "J8") (pin "70") (pinfunction "70_70") (pintype "passive"))
    )
    (net (code "161") (name "/P33.0") (class "Default")
      (node (ref "J21") (pin "1") (pinfunction "1_1") (pintype "passive"))
      (node (ref "J7") (pin "66") (pinfunction "66_66") (pintype "passive"))
    )
    (net (code "162") (name "/P33.1") (class "Default")
      (node (ref "J21") (pin "3") (pinfunction "3_3") (pintype "passive"))
      (node (ref "J7") (pin "67") (pinfunction "67_67") (pintype "passive"))
    )
    (net (code "163") (name "/P33.2") (class "Default")
      (node (ref "J21") (pin "5") (pinfunction "5_5") (pintype "passive"))
      (node (ref "J7") (pin "65") (pinfunction "65_65") (pintype "passive"))
    )
    (net (code "164") (name "/P33.3") (class "Default")
      (node (ref "J21") (pin "7") (pinfunction "7_7") (pintype "passive"))
      (node (ref "J7") (pin "63") (pinfunction "63_63") (pintype "passive"))
    )
    (net (code "165") (name "/P33.4") (class "Default")
      (node (ref "J21") (pin "9") (pinfunction "9_9") (pintype "passive"))
      (node (ref "J7") (pin "68") (pinfunction "68_68") (pintype "passive"))
    )
    (net (code "166") (name "/P33.5") (class "Default")
      (node (ref "J21") (pin "11") (pinfunction "11_11") (pintype "passive"))
      (node (ref "J6") (pin "41") (pinfunction "41_41") (pintype "passive"))
    )
    (net (code "167") (name "/P33.6") (class "Default")
      (node (ref "J21") (pin "13") (pinfunction "13_13") (pintype "passive"))
      (node (ref "J7") (pin "64") (pinfunction "64_64") (pintype "passive"))
    )
    (net (code "168") (name "/P33.7") (class "Default")
      (node (ref "J21") (pin "15") (pinfunction "15_15") (pintype "passive"))
      (node (ref "J7") (pin "77") (pinfunction "77_77") (pintype "passive"))
    )
    (net (code "169") (name "/P33.8") (class "Default")
      (node (ref "J21") (pin "2") (pinfunction "2_2") (pintype "passive"))
      (node (ref "J8") (pin "56") (pinfunction "56_56") (pintype "passive"))
    )
    (net (code "170") (name "/P33.9") (class "Default")
      (node (ref "J21") (pin "4") (pinfunction "4_4") (pintype "passive"))
      (node (ref "J8") (pin "58") (pinfunction "58_58") (pintype "passive"))
    )
    (net (code "171") (name "/P33.10") (class "Default")
      (node (ref "J21") (pin "6") (pinfunction "6_6") (pintype "passive"))
      (node (ref "J8") (pin "60") (pinfunction "60_60") (pintype "passive"))
    )
    (net (code "172") (name "/P33.11") (class "Default")
      (node (ref "J21") (pin "8") (pinfunction "8_8") (pintype "passive"))
      (node (ref "J7") (pin "79") (pinfunction "79_79") (pintype "passive"))
    )
    (net (code "173") (name "/P33.12") (class "Default")
      (node (ref "J21") (pin "10") (pinfunction "10_10") (pintype "passive"))
      (node (ref "J7") (pin "80") (pinfunction "80_80") (pintype "passive"))
    )
    (net (code "174") (name "/P33.13") (class "Default")
      (node (ref "J21") (pin "12") (pinfunction "12_12") (pintype "passive"))
      (node (ref "J8") (pin "62") (pinfunction "62_62") (pintype "passive"))
    )
    (net (code "175") (name "/P33.14") (class "Default")
      (node (ref "J21") (pin "14") (pinfunction "14_14") (pintype "passive"))
      (node (ref "J8") (pin "64") (pinfunction "64_64") (pintype "passive"))
    )
    (net (code "176") (name "/P33.15") (class "Default")
      (node (ref "J21") (pin "16") (pinfunction "16_16") (pintype "passive"))
      (node (ref "J8") (pin "66") (pinfunction "66_66") (pintype "passive"))
    )
    (net (code "177") (name "/P34.1") (class "Default")
      (node (ref "J4") (pin "1") (pinfunction "1_1") (pintype "passive"))
      (node (ref "J8") (pin "69") (pinfunction "69_69") (pintype "passive"))
    )
    (net (code "178") (name "/P34.2") (class "Default")
      (node (ref "J4") (pin "3") (pinfunction "3_3") (pintype "passive"))
      (node (ref "J8") (pin "71") (pinfunction "71_71") (pintype "passive"))
    )
    (net (code "179") (name "/P34.3") (class "Default")
      (node (ref "J4") (pin "5") (pinfunction "5_5") (pintype "passive"))
      (node (ref "J8") (pin "73") (pinfunction "73_73") (pintype "passive"))
    )
    (net (code "180") (name "/P34.4") (class "Default")
      (node (ref "J4") (pin "2") (pinfunction "2_2") (pintype "passive"))
      (node (ref "J8") (pin "72") (pinfunction "72_72") (pintype "passive"))
    )
    (net (code "181") (name "/P34.5") (class "Default")
      (node (ref "J4") (pin "4") (pinfunction "4_4") (pintype "passive"))
      (node (ref "J8") (pin "74") (pinfunction "74_74") (pintype "passive"))
    )
    (net (code "182") (name "/VAREF1") (class "Default")
      (node (ref "J17") (pin "3") (pinfunction "3_3") (pintype "passive"))
      (node (ref "J7") (pin "40") (pinfunction "40_40") (pintype "passive"))
    )
    (net (code "183") (name "/VAREF2") (class "Default")
      (node (ref "J17") (pin "4") (pinfunction "4_4") (pintype "passive"))
      (node (ref "J7") (pin "42") (pinfunction "42_42") (pintype "passive"))
    )
    (net (code "184") (name "/VCC_IN") (class "Default")
      (node (ref "J17") (pin "7") (pinfunction "7_7") (pintype "passive"))
      (node (ref "J6") (pin "05") (pinfunction "05_05") (pintype "passive"))
      (node (ref "J6") (pin "06") (pinfunction "06_06") (pintype "passive"))
      (node (ref "J6") (pin "07") (pinfunction "07_07") (pintype "passive"))
      (node (ref "J6") (pin "08") (pinfunction "08_08") (pintype "passive"))
    )
    (net (code "185") (name "/VDDM") (class "Default")
      (node (ref "J17") (pin "10") (pinfunction "10_10") (pintype "passive"))
      (node (ref "J7") (pin "39") (pinfunction "39_39") (pintype "passive"))
    )
    (net (code "186") (name "/VDDSB") (class "Default")
      (node (ref "J17") (pin "11") (pinfunction "11_11") (pintype "passive"))
      (node (ref "J6") (pin "75") (pinfunction "75_75") (pintype "passive"))
    )
    (net (code "187") (name "/VEXT") (class "Default")
      (node (ref "J17") (pin "8") (pinfunction "8_8") (pintype "passive"))
      (node (ref "J6") (pin "77") (pinfunction "77_77") (pintype "passive"))
      (node (ref "J6") (pin "79") (pinfunction "79_79") (pintype "passive"))
      (node (ref "J7") (pin "69") (pinfunction "69_69") (pintype "passive"))
      (node (ref "J8") (pin "77") (pinfunction "77_77") (pintype "passive"))
      (node (ref "J8") (pin "79") (pinfunction "79_79") (pintype "passive"))
    )
    (net (code "188") (name "/VFLEX") (class "Default")
      (node (ref "J17") (pin "9") (pinfunction "9_9") (pintype "passive"))
      (node (ref "J8") (pin "75") (pinfunction "75_75") (pintype "passive"))
    )
    (net (code "189") (name "/XTAL1") (class "Default")
      (node (ref "J17") (pin "1") (pinfunction "1_1") (pintype "passive"))
      (node (ref "J6") (pin "51") (pinfunction "51_51") (pintype "passive"))
    )
    (net (code "190") (name "/XTAL2") (class "Default")
      (node (ref "J17") (pin "2") (pinfunction "2_2") (pintype "passive"))
      (node (ref "J6") (pin "53") (pinfunction "53_53") (pintype "passive"))
    )
    (net (code "191") (name "/{slash}ESR0") (class "Default")
      (node (ref "J17") (pin "5") (pinfunction "5_5") (pintype "passive"))
      (node (ref "J6") (pin "16") (pinfunction "16_16") (pintype "passive"))
    )
    (net (code "192") (name "/{slash}ESR1") (class "Default")
      (node (ref "J17") (pin "6") (pinfunction "6_6") (pintype "passive"))
      (node (ref "J6") (pin "15") (pinfunction "15_15") (pintype "passive"))
    )
    (net (code "193") (name "/{slash}PORST") (class "Default")
      (node (ref "J17") (pin "12") (pinfunction "12_12") (pintype "passive"))
      (node (ref "J6") (pin "22") (pinfunction "22_22") (pintype "passive"))
    )
    (net (code "194") (name "GND") (class "Default")
      (node (ref "J1") (pin "10") (pinfunction "10_10") (pintype "passive"))
      (node (ref "J10") (pin "6") (pinfunction "6_6") (pintype "passive"))
      (node (ref "J12") (pin "10") (pinfunction "10_10") (pintype "passive"))
      (node (ref "J16") (pin "14") (pinfunction "14_14") (pintype "passive"))
      (node (ref "J2") (pin "4") (pinfunction "4_4") (pintype "passive"))
      (node (ref "J24") (pin "1") (pinfunction "1_1") (pintype "passive"))
      (node (ref "J24") (pin "2") (pinfunction "2_2") (pintype "passive"))
      (node (ref "J24") (pin "3") (pinfunction "3_3") (pintype "passive"))
      (node (ref "J24") (pin "4") (pinfunction "4_4") (pintype "passive"))
      (node (ref "J24") (pin "5") (pinfunction "5_5") (pintype "passive"))
      (node (ref "J24") (pin "6") (pinfunction "6_6") (pintype "passive"))
      (node (ref "J24") (pin "7") (pinfunction "7_7") (pintype "passive"))
      (node (ref "J24") (pin "8") (pinfunction "8_8") (pintype "passive"))
      (node (ref "J27") (pin "8") (pinfunction "8_8") (pintype "passive"))
      (node (ref "J3") (pin "14") (pinfunction "14_14") (pintype "passive"))
      (node (ref "J4") (pin "6") (pinfunction "6_6") (pintype "passive"))
      (node (ref "J5") (pin "01") (pinfunction "01_01") (pintype "passive"))
      (node (ref "J5") (pin "02") (pinfunction "02_02") (pintype "passive"))
      (node (ref "J5") (pin "03") (pinfunction "03_03") (pintype "passive"))
      (node (ref "J5") (pin "04") (pinfunction "04_04") (pintype "passive"))
      (node (ref "J6") (pin "01") (pinfunction "01_01") (pintype "passive"))
      (node (ref "J6") (pin "02") (pinfunction "02_02") (pintype "passive"))
      (node (ref "J6") (pin "03") (pinfunction "03_03") (pintype "passive"))
      (node (ref "J6") (pin "04") (pinfunction "04_04") (pintype "passive"))
      (node (ref "J6") (pin "19") (pinfunction "19_19") (pintype "passive"))
      (node (ref "J6") (pin "20") (pinfunction "20_20") (pintype "passive"))
      (node (ref "J6") (pin "49") (pinfunction "49_49") (pintype "passive"))
      (node (ref "J6") (pin "50") (pinfunction "50_50") (pintype "passive"))
      (node (ref "J6") (pin "76") (pinfunction "76_76") (pintype "passive"))
      (node (ref "J7") (pin "01") (pinfunction "01_01") (pintype "passive"))
      (node (ref "J7") (pin "02") (pinfunction "02_02") (pintype "passive"))
      (node (ref "J7") (pin "03") (pinfunction "03_03") (pintype "passive"))
      (node (ref "J7") (pin "04") (pinfunction "04_04") (pintype "passive"))
      (node (ref "J7") (pin "37") (pinfunction "37_37") (pintype "passive"))
      (node (ref "J7") (pin "38") (pinfunction "38_38") (pintype "passive"))
      (node (ref "J7") (pin "41") (pinfunction "41_41") (pintype "passive"))
      (node (ref "J7") (pin "43") (pinfunction "43_43") (pintype "passive"))
      (node (ref "J7") (pin "44") (pinfunction "44_44") (pintype "passive"))
      (node (ref "J7") (pin "61") (pinfunction "61_61") (pintype "passive"))
      (node (ref "J7") (pin "62") (pinfunction "62_62") (pintype "passive"))
      (node (ref "J8") (pin "01") (pinfunction "01_01") (pintype "passive"))
      (node (ref "J8") (pin "02") (pinfunction "02_02") (pintype "passive"))
      (node (ref "J8") (pin "03") (pinfunction "03_03") (pintype "passive"))
      (node (ref "J8") (pin "04") (pinfunction "04_04") (pintype "passive"))
    )
    (net (code "195") (name "unconnected-(J5-Pad05)") (class "Default")
      (node (ref "J5") (pin "05") (pinfunction "05_05") (pintype "passive+no_connect"))
    )
    (net (code "196") (name "unconnected-(J5-Pad07)") (class "Default")
      (node (ref "J5") (pin "07") (pinfunction "07_07") (pintype "passive+no_connect"))
    )
    (net (code "197") (name "unconnected-(J5-Pad09)") (class "Default")
      (node (ref "J5") (pin "09") (pinfunction "09_09") (pintype "passive+no_connect"))
    )
    (net (code "198") (name "unconnected-(J5-Pad10)") (class "Default")
      (node (ref "J5") (pin "10") (pinfunction "10_10") (pintype "passive+no_connect"))
    )
    (net (code "199") (name "unconnected-(J5-Pad11)") (class "Default")
      (node (ref "J5") (pin "11") (pinfunction "11_11") (pintype "passive+no_connect"))
    )
    (net (code "200") (name "unconnected-(J5-Pad12)") (class "Default")
      (node (ref "J5") (pin "12") (pinfunction "12_12") (pintype "passive+no_connect"))
    )
    (net (code "201") (name "unconnected-(J5-Pad13)") (class "Default")
      (node (ref "J5") (pin "13") (pinfunction "13_13") (pintype "passive+no_connect"))
    )
    (net (code "202") (name "unconnected-(J5-Pad14)") (class "Default")
      (node (ref "J5") (pin "14") (pinfunction "14_14") (pintype "passive+no_connect"))
    )
    (net (code "203") (name "unconnected-(J5-Pad15)") (class "Default")
      (node (ref "J5") (pin "15") (pinfunction "15_15") (pintype "passive+no_connect"))
    )
    (net (code "204") (name "unconnected-(J5-Pad16)") (class "Default")
      (node (ref "J5") (pin "16") (pinfunction "16_16") (pintype "passive+no_connect"))
    )
    (net (code "205") (name "unconnected-(J5-Pad17)") (class "Default")
      (node (ref "J5") (pin "17") (pinfunction "17_17") (pintype "passive+no_connect"))
    )
    (net (code "206") (name "unconnected-(J5-Pad18)") (class "Default")
      (node (ref "J5") (pin "18") (pinfunction "18_18") (pintype "passive+no_connect"))
    )
    (net (code "207") (name "unconnected-(J5-Pad19)") (class "Default")
      (node (ref "J5") (pin "19") (pinfunction "19_19") (pintype "passive+no_connect"))
    )
    (net (code "208") (name "unconnected-(J5-Pad20)") (class "Default")
      (node (ref "J5") (pin "20") (pinfunction "20_20") (pintype "passive+no_connect"))
    )
    (net (code "209") (name "unconnected-(J5-Pad21)") (class "Default")
      (node (ref "J5") (pin "21") (pinfunction "21_21") (pintype "passive+no_connect"))
    )
    (net (code "210") (name "unconnected-(J5-Pad22)") (class "Default")
      (node (ref "J5") (pin "22") (pinfunction "22_22") (pintype "passive+no_connect"))
    )
    (net (code "211") (name "unconnected-(J5-Pad23)") (class "Default")
      (node (ref "J5") (pin "23") (pinfunction "23_23") (pintype "passive+no_connect"))
    )
    (net (code "212") (name "unconnected-(J5-Pad24)") (class "Default")
      (node (ref "J5") (pin "24") (pinfunction "24_24") (pintype "passive+no_connect"))
    )
    (net (code "213") (name "unconnected-(J5-Pad25)") (class "Default")
      (node (ref "J5") (pin "25") (pinfunction "25_25") (pintype "passive+no_connect"))
    )
    (net (code "214") (name "unconnected-(J5-Pad26)") (class "Default")
      (node (ref "J5") (pin "26") (pinfunction "26_26") (pintype "passive+no_connect"))
    )
    (net (code "215") (name "unconnected-(J5-Pad27)") (class "Default")
      (node (ref "J5") (pin "27") (pinfunction "27_27") (pintype "passive+no_connect"))
    )
    (net (code "216") (name "unconnected-(J5-Pad28)") (class "Default")
      (node (ref "J5") (pin "28") (pinfunction "28_28") (pintype "passive+no_connect"))
    )
    (net (code "217") (name "unconnected-(J5-Pad29)") (class "Default")
      (node (ref "J5") (pin "29") (pinfunction "29_29") (pintype "passive+no_connect"))
    )
    (net (code "218") (name "unconnected-(J5-Pad30)") (class "Default")
      (node (ref "J5") (pin "30") (pinfunction "30_30") (pintype "passive+no_connect"))
    )
    (net (code "219") (name "unconnected-(J5-Pad31)") (class "Default")
      (node (ref "J5") (pin "31") (pinfunction "31_31") (pintype "passive+no_connect"))
    )
    (net (code "220") (name "unconnected-(J5-Pad32)") (class "Default")
      (node (ref "J5") (pin "32") (pinfunction "32_32") (pintype "passive+no_connect"))
    )
    (net (code "221") (name "unconnected-(J5-Pad33)") (class "Default")
      (node (ref "J5") (pin "33") (pinfunction "33_33") (pintype "passive+no_connect"))
    )
    (net (code "222") (name "unconnected-(J5-Pad34)") (class "Default")
      (node (ref "J5") (pin "34") (pinfunction "34_34") (pintype "passive+no_connect"))
    )
    (net (code "223") (name "unconnected-(J5-Pad35)") (class "Default")
      (node (ref "J5") (pin "35") (pinfunction "35_35") (pintype "passive+no_connect"))
    )
    (net (code "224") (name "unconnected-(J5-Pad36)") (class "Default")
      (node (ref "J5") (pin "36") (pinfunction "36_36") (pintype "passive+no_connect"))
    )
    (net (code "225") (name "unconnected-(J5-Pad37)") (class "Default")
      (node (ref "J5") (pin "37") (pinfunction "37_37") (pintype "passive+no_connect"))
    )
    (net (code "226") (name "unconnected-(J5-Pad38)") (class "Default")
      (node (ref "J5") (pin "38") (pinfunction "38_38") (pintype "passive+no_connect"))
    )
    (net (code "227") (name "unconnected-(J5-Pad39)") (class "Default")
      (node (ref "J5") (pin "39") (pinfunction "39_39") (pintype "passive+no_connect"))
    )
    (net (code "228") (name "unconnected-(J5-Pad40)") (class "Default")
      (node (ref "J5") (pin "40") (pinfunction "40_40") (pintype "passive+no_connect"))
    )
    (net (code "229") (name "unconnected-(J5-Pad41)") (class "Default")
      (node (ref "J5") (pin "41") (pinfunction "41_41") (pintype "passive+no_connect"))
    )
    (net (code "230") (name "unconnected-(J5-Pad42)") (class "Default")
      (node (ref "J5") (pin "42") (pinfunction "42_42") (pintype "passive+no_connect"))
    )
    (net (code "231") (name "unconnected-(J5-Pad43)") (class "Default")
      (node (ref "J5") (pin "43") (pinfunction "43_43") (pintype "passive+no_connect"))
    )
    (net (code "232") (name "unconnected-(J5-Pad44)") (class "Default")
      (node (ref "J5") (pin "44") (pinfunction "44_44") (pintype "passive+no_connect"))
    )
    (net (code "233") (name "unconnected-(J5-Pad45)") (class "Default")
      (node (ref "J5") (pin "45") (pinfunction "45_45") (pintype "passive+no_connect"))
    )
    (net (code "234") (name "unconnected-(J5-Pad46)") (class "Default")
      (node (ref "J5") (pin "46") (pinfunction "46_46") (pintype "passive+no_connect"))
    )
    (net (code "235") (name "unconnected-(J5-Pad47)") (class "Default")
      (node (ref "J5") (pin "47") (pinfunction "47_47") (pintype "passive+no_connect"))
    )
    (net (code "236") (name "unconnected-(J5-Pad48)") (class "Default")
      (node (ref "J5") (pin "48") (pinfunction "48_48") (pintype "passive+no_connect"))
    )
    (net (code "237") (name "unconnected-(J5-Pad49)") (class "Default")
      (node (ref "J5") (pin "49") (pinfunction "49_49") (pintype "passive+no_connect"))
    )
    (net (code "238") (name "unconnected-(J5-Pad51)") (class "Default")
      (node (ref "J5") (pin "51") (pinfunction "51_51") (pintype "passive+no_connect"))
    )
    (net (code "239") (name "unconnected-(J5-Pad53)") (class "Default")
      (node (ref "J5") (pin "53") (pinfunction "53_53") (pintype "passive+no_connect"))
    )
    (net (code "240") (name "unconnected-(J5-Pad55)") (class "Default")
      (node (ref "J5") (pin "55") (pinfunction "55_55") (pintype "passive+no_connect"))
    )
    (net (code "241") (name "unconnected-(J5-Pad57)") (class "Default")
      (node (ref "J5") (pin "57") (pinfunction "57_57") (pintype "passive+no_connect"))
    )
    (net (code "242") (name "unconnected-(J5-Pad58)") (class "Default")
      (node (ref "J5") (pin "58") (pinfunction "58_58") (pintype "passive+no_connect"))
    )
    (net (code "243") (name "unconnected-(J5-Pad59)") (class "Default")
      (node (ref "J5") (pin "59") (pinfunction "59_59") (pintype "passive+no_connect"))
    )
    (net (code "244") (name "unconnected-(J5-Pad60)") (class "Default")
      (node (ref "J5") (pin "60") (pinfunction "60_60") (pintype "passive+no_connect"))
    )
    (net (code "245") (name "unconnected-(J5-Pad61)") (class "Default")
      (node (ref "J5") (pin "61") (pinfunction "61_61") (pintype "passive+no_connect"))
    )
    (net (code "246") (name "unconnected-(J5-Pad62)") (class "Default")
      (node (ref "J5") (pin "62") (pinfunction "62_62") (pintype "passive+no_connect"))
    )
    (net (code "247") (name "unconnected-(J5-Pad63)") (class "Default")
      (node (ref "J5") (pin "63") (pinfunction "63_63") (pintype "passive+no_connect"))
    )
    (net (code "248") (name "unconnected-(J5-Pad64)") (class "Default")
      (node (ref "J5") (pin "64") (pinfunction "64_64") (pintype "passive+no_connect"))
    )
    (net (code "249") (name "unconnected-(J5-Pad65)") (class "Default")
      (node (ref "J5") (pin "65") (pinfunction "65_65") (pintype "passive+no_connect"))
    )
    (net (code "250") (name "unconnected-(J5-Pad66)") (class "Default")
      (node (ref "J5") (pin "66") (pinfunction "66_66") (pintype "passive+no_connect"))
    )
    (net (code "251") (name "unconnected-(J5-Pad67)") (class "Default")
      (node (ref "J5") (pin "67") (pinfunction "67_67") (pintype "passive+no_connect"))
    )
    (net (code "252") (name "unconnected-(J5-Pad68)") (class "Default")
      (node (ref "J5") (pin "68") (pinfunction "68_68") (pintype "passive+no_connect"))
    )
    (net (code "253") (name "unconnected-(J5-Pad69)") (class "Default")
      (node (ref "J5") (pin "69") (pinfunction "69_69") (pintype "passive+no_connect"))
    )
    (net (code "254") (name "unconnected-(J5-Pad70)") (class "Default")
      (node (ref "J5") (pin "70") (pinfunction "70_70") (pintype "passive+no_connect"))
    )
    (net (code "255") (name "unconnected-(J5-Pad71)") (class "Default")
      (node (ref "J5") (pin "71") (pinfunction "71_71") (pintype "passive+no_connect"))
    )
    (net (code "256") (name "unconnected-(J5-Pad73)") (class "Default")
      (node (ref "J5") (pin "73") (pinfunction "73_73") (pintype "passive+no_connect"))
    )
    (net (code "257") (name "unconnected-(J5-Pad74)") (class "Default")
      (node (ref "J5") (pin "74") (pinfunction "74_74") (pintype "passive+no_connect"))
    )
    (net (code "258") (name "unconnected-(J5-Pad75)") (class "Default")
      (node (ref "J5") (pin "75") (pinfunction "75_75") (pintype "passive+no_connect"))
    )
    (net (code "259") (name "unconnected-(J5-Pad76)") (class "Default")
      (node (ref "J5") (pin "76") (pinfunction "76_76") (pintype "passive+no_connect"))
    )
    (net (code "260") (name "unconnected-(J5-Pad77)") (class "Default")
      (node (ref "J5") (pin "77") (pinfunction "77_77") (pintype "passive+no_connect"))
    )
    (net (code "261") (name "unconnected-(J5-Pad78)") (class "Default")
      (node (ref "J5") (pin "78") (pinfunction "78_78") (pintype "passive+no_connect"))
    )
    (net (code "262") (name "unconnected-(J6-Pad21)") (class "Default")
      (node (ref "J6") (pin "21") (pinfunction "21_21") (pintype "passive+no_connect"))
    )
    (net (code "263") (name "unconnected-(J6-Pad54)") (class "Default")
      (node (ref "J6") (pin "54") (pinfunction "54_54") (pintype "passive+no_connect"))
    )
    (net (code "264") (name "unconnected-(J8-Pad10)") (class "Default")
      (node (ref "J8") (pin "10") (pinfunction "10_10") (pintype "passive+no_connect"))
    )
    (net (code "265") (name "unconnected-(J8-Pad12)") (class "Default")
      (node (ref "J8") (pin "12") (pinfunction "12_12") (pintype "passive+no_connect"))
    )
    (net (code "266") (name "unconnected-(J8-Pad14)") (class "Default")
      (node (ref "J8") (pin "14") (pinfunction "14_14") (pintype "passive+no_connect"))
    )
    (net (code "267") (name "unconnected-(J8-Pad16)") (class "Default")
      (node (ref "J8") (pin "16") (pinfunction "16_16") (pintype "passive+no_connect"))
    )
    (net (code "268") (name "unconnected-(J8-Pad41)") (class "Default")
      (node (ref "J8") (pin "41") (pinfunction "41_41") (pintype "passive+no_connect"))
    )
    (net (code "269") (name "unconnected-(J8-Pad43)") (class "Default")
      (node (ref "J8") (pin "43") (pinfunction "43_43") (pintype "passive+no_connect"))
    )
    (net (code "270") (name "unconnected-(J8-Pad45)") (class "Default")
      (node (ref "J8") (pin "45") (pinfunction "45_45") (pintype "passive+no_connect"))
    )
    (net (code "271") (name "unconnected-(J8-Pad46)") (class "Default")
      (node (ref "J8") (pin "46") (pinfunction "46_46") (pintype "passive+no_connect"))
    )
    (net (code "272") (name "unconnected-(J8-Pad47)") (class "Default")
      (node (ref "J8") (pin "47") (pinfunction "47_47") (pintype "passive+no_connect"))
    )
    (net (code "273") (name "unconnected-(J8-Pad48)") (class "Default")
      (node (ref "J8") (pin "48") (pinfunction "48_48") (pintype "passive+no_connect"))
    )
    (net (code "274") (name "unconnected-(J8-Pad49)") (class "Default")
      (node (ref "J8") (pin "49") (pinfunction "49_49") (pintype "passive+no_connect"))
    )
    (net (code "275") (name "unconnected-(J8-Pad51)") (class "Default")
      (node (ref "J8") (pin "51") (pinfunction "51_51") (pintype "passive+no_connect"))
    )
    (net (code "276") (name "unconnected-(J8-Pad53)") (class "Default")
      (node (ref "J8") (pin "53") (pinfunction "53_53") (pintype "passive+no_connect"))
    )
    (net (code "277") (name "unconnected-(J8-Pad55)") (class "Default")
      (node (ref "J8") (pin "55") (pinfunction "55_55") (pintype "passive+no_connect"))
    )
    (net (code "278") (name "unconnected-(J8-Pad57)") (class "Default")
      (node (ref "J8") (pin "57") (pinfunction "57_57") (pintype "passive+no_connect"))
    )
    (net (code "279") (name "unconnected-(J8-Pad59)") (class "Default")
      (node (ref "J8") (pin "59") (pinfunction "59_59") (pintype "passive+no_connect"))
    )
    (net (code "280") (name "unconnected-(J8-Pad61)") (class "Default")
      (node (ref "J8") (pin "61") (pinfunction "61_61") (pintype "passive+no_connect"))
    )
    (net (code "281") (name "unconnected-(J8-Pad63)") (class "Default")
      (node (ref "J8") (pin "63") (pinfunction "63_63") (pintype "passive+no_connect"))
    )
    (net (code "282") (name "unconnected-(J8-Pad65)") (class "Default")
      (node (ref "J8") (pin "65") (pinfunction "65_65") (pintype "passive+no_connect"))
    )
  )
)
